# strobe-pcb.net
KiCad netlist of a schematic drawn in EAGLE
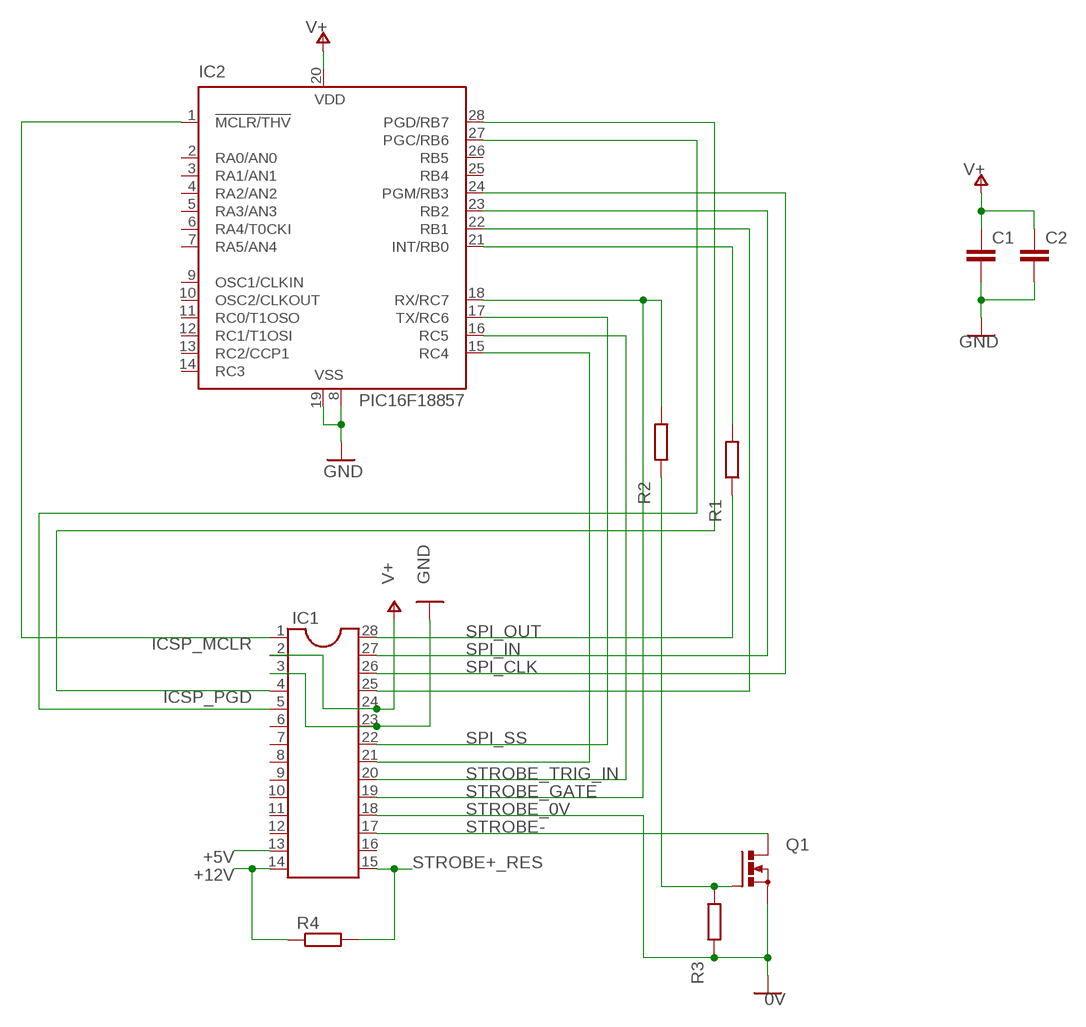
[diagram p0: schematic, sheet 1]

(export (version "E")
  (design (tool "Eeschema 10.0.6"))
  (components
    (comp (ref "C1")
      (value "C-EUC1206")
      (footprint "eagle-import:C1206")
      (libsource (lib "eagle-import") (part "C-EUC1206"))
    )
    (comp (ref "C2")
      (value "C-EUC1206")
      (footprint "eagle-import:C1206")
      (libsource (lib "eagle-import") (part "C-EUC1206"))
    )
    (comp (ref "IC1")
      (value "DIL28")
      (footprint "eagle-import:DIL28-6")
      (libsource (lib "eagle-import") (part "DIL28"))
    )
    (comp (ref "IC2")
      (value "PIC16F18857")
      (footprint "eagle-import:SO28W")
      (fields (field (name "MF") "MICROCHIP") (field (name "MPN") "PIC16F870-I/SO"))
      (libsource (lib "eagle-import") (part "PIC16870SOF"))
    )
    (comp (ref "Q1")
      (value "PMOSFET_NTO220BV")
      (footprint "eagle-import:TO220BV")
      (libsource (lib "eagle-import") (part "PMOSFET_NTO220BV"))
    )
    (comp (ref "R1")
      (value "R-EU_R1206")
      (footprint "eagle-import:R1206")
      (libsource (lib "eagle-import") (part "R-EU_R1206"))
    )
    (comp (ref "R2")
      (value "R-EU_R1206")
      (footprint "eagle-import:R1206")
      (libsource (lib "eagle-import") (part "R-EU_R1206"))
    )
    (comp (ref "R3")
      (value "R-EU_R1206")
      (footprint "eagle-import:R1206")
      (libsource (lib "eagle-import") (part "R-EU_R1206"))
    )
    (comp (ref "R4")
      (value "R-EU_0207/10")
      (footprint "eagle-import:0207_10")
      (libsource (lib "eagle-import") (part "R-EU_0207/10"))
    )
  )
  (nets
    (net (code "1") (name "/+5V") (class "Default")
      (node (ref "IC1") (pin "13") (pinfunction "13_13") (pintype "passive"))
    )
    (net (code "2") (name "/+12V") (class "Default")
      (node (ref "IC1") (pin "14") (pinfunction "14_14") (pintype "passive"))
      (node (ref "R4") (pin "1") (pinfunction "1_1") (pintype "passive"))
    )
    (net (code "3") (name "/ICSP_MCLR") (class "Default")
      (node (ref "IC1") (pin "1") (pinfunction "1_1") (pintype "passive"))
      (node (ref "IC2") (pin "1") (pinfunction "~{MCLR/THV}_1") (pintype "input"))
    )
    (net (code "4") (name "/ICSP_PGD") (class "Default")
      (node (ref "IC1") (pin "4") (pinfunction "4_4") (pintype "passive"))
      (node (ref "IC2") (pin "28") (pinfunction "PGD/RB7_28") (pintype "bidirectional"))
    )
    (net (code "5") (name "/SPI_CLK") (class "Default")
      (node (ref "IC1") (pin "26") (pinfunction "26_26") (pintype "passive"))
      (node (ref "IC2") (pin "24") (pinfunction "PGM/RB3_24") (pintype "bidirectional"))
    )
    (net (code "6") (name "/SPI_IN") (class "Default")
      (node (ref "IC1") (pin "27") (pinfunction "27_27") (pintype "passive"))
      (node (ref "IC2") (pin "23") (pinfunction "RB2_23") (pintype "bidirectional"))
    )
    (net (code "7") (name "/SPI_OUT") (class "Default")
      (node (ref "IC1") (pin "28") (pinfunction "28_28") (pintype "passive"))
      (node (ref "R1") (pin "1") (pinfunction "1_1") (pintype "passive"))
    )
    (net (code "8") (name "/SPI_SS") (class "Default")
      (node (ref "IC1") (pin "22") (pinfunction "22_22") (pintype "passive"))
      (node (ref "IC2") (pin "17") (pinfunction "TX/RC6_17") (pintype "bidirectional"))
    )
    (net (code "9") (name "/STROBE+_RES") (class "Default")
      (node (ref "IC1") (pin "15") (pinfunction "15_15") (pintype "passive"))
      (node (ref "R4") (pin "2") (pinfunction "2_2") (pintype "passive"))
    )
    (net (code "10") (name "/STROBE-") (class "Default")
      (node (ref "IC1") (pin "17") (pinfunction "17_17") (pintype "passive"))
      (node (ref "Q1") (pin "D") (pinfunction "D_D") (pintype "passive"))
    )
    (net (code "11") (name "/STROBE_GATE") (class "Default")
      (node (ref "IC1") (pin "19") (pinfunction "19_19") (pintype "passive"))
      (node (ref "IC2") (pin "18") (pinfunction "RX/RC7_18") (pintype "bidirectional"))
      (node (ref "R2") (pin "2") (pinfunction "2_2") (pintype "passive"))
    )
    (net (code "12") (name "/STROBE_TRIG_IN") (class "Default")
      (node (ref "IC1") (pin "20") (pinfunction "20_20") (pintype "passive"))
      (node (ref "IC2") (pin "16") (pinfunction "RC5_16") (pintype "bidirectional"))
    )
    (net (code "13") (name "0V") (class "Default")
      (node (ref "IC1") (pin "18") (pinfunction "18_18") (pintype "passive"))
      (node (ref "Q1") (pin "S") (pinfunction "S_S") (pintype "passive"))
      (node (ref "R3") (pin "1") (pinfunction "1_1") (pintype "passive"))
    )
    (net (code "14") (name "GND") (class "Default")
      (node (ref "C1") (pin "2") (pinfunction "2_2") (pintype "passive"))
      (node (ref "C2") (pin "2") (pinfunction "2_2") (pintype "passive"))
      (node (ref "IC1") (pin "23") (pinfunction "23_23") (pintype "passive"))
      (node (ref "IC1") (pin "3") (pinfunction "3_3") (pintype "passive"))
      (node (ref "IC2") (pin "19") (pinfunction "VSS_19") (pintype "power_in"))
      (node (ref "IC2") (pin "8") (pinfunction "VSS_8") (pintype "power_in"))
    )
    (net (code "15") (name "Net-(IC2-INT{slash}RB0)") (class "Default")
      (node (ref "IC2") (pin "21") (pinfunction "INT/RB0_21") (pintype "bidirectional"))
      (node (ref "R1") (pin "2") (pinfunction "2_2") (pintype "passive"))
    )
    (net (code "16") (name "Net-(IC2-PGC{slash}RB6)") (class "Default")
      (node (ref "IC1") (pin "5") (pinfunction "5_5") (pintype "passive"))
      (node (ref "IC2") (pin "27") (pinfunction "PGC/RB6_27") (pintype "bidirectional"))
    )
    (net (code "17") (name "Net-(IC2-RB1)") (class "Default")
      (node (ref "IC1") (pin "25") (pinfunction "25_25") (pintype "passive"))
      (node (ref "IC2") (pin "22") (pinfunction "RB1_22") (pintype "bidirectional"))
    )
    (net (code "18") (name "Net-(IC2-RC4)") (class "Default")
      (node (ref "IC1") (pin "21") (pinfunction "21_21") (pintype "passive"))
      (node (ref "IC2") (pin "15") (pinfunction "RC4_15") (pintype "bidirectional"))
    )
    (net (code "19") (name "Net-(Q1-PadG)") (class "Default")
      (node (ref "Q1") (pin "G") (pinfunction "G_G") (pintype "passive"))
      (node (ref "R2") (pin "1") (pinfunction "1_1") (pintype "passive"))
      (node (ref "R3") (pin "2") (pinfunction "2_2") (pintype "passive"))
    )
    (net (code "20") (name "V+") (class "Default")
      (node (ref "C1") (pin "1") (pinfunction "1_1") (pintype "passive"))
      (node (ref "C2") (pin "1") (pinfunction "1_1") (pintype "passive"))
      (node (ref "IC1") (pin "2") (pinfunction "2_2") (pintype "passive"))
      (node (ref "IC1") (pin "24") (pinfunction "24_24") (pintype "passive"))
      (node (ref "IC2") (pin "20") (pinfunction "VDD_20") (pintype "power_in"))
    )
    (net (code "21") (name "unconnected-(IC1-Pad6)") (class "Default")
      (node (ref "IC1") (pin "6") (pinfunction "6_6") (pintype "passive"))
    )
    (net (code "22") (name "unconnected-(IC1-Pad7)") (class "Default")
      (node (ref "IC1") (pin "7") (pinfunction "7_7") (pintype "passive"))
    )
    (net (code "23") (name "unconnected-(IC1-Pad8)") (class "Default")
      (node (ref "IC1") (pin "8") (pinfunction "8_8") (pintype "passive"))
    )
    (net (code "24") (name "unconnected-(IC1-Pad9)") (class "Default")
      (node (ref "IC1") (pin "9") (pinfunction "9_9") (pintype "passive"))
    )
    (net (code "25") (name "unconnected-(IC1-Pad10)") (class "Default")
      (node (ref "IC1") (pin "10") (pinfunction "10_10") (pintype "passive"))
    )
    (net (code "26") (name "unconnected-(IC1-Pad11)") (class "Default")
      (node (ref "IC1") (pin "11") (pinfunction "11_11") (pintype "passive"))
    )
    (net (code "27") (name "unconnected-(IC1-Pad12)") (class "Default")
      (node (ref "IC1") (pin "12") (pinfunction "12_12") (pintype "passive"))
    )
    (net (code "28") (name "unconnected-(IC1-Pad16)") (class "Default")
      (node (ref "IC1") (pin "16") (pinfunction "16_16") (pintype "passive"))
    )
    (net (code "29") (name "unconnected-(IC2-OSC1{slash}CLKIN-Pad9)") (class "Default")
      (node (ref "IC2") (pin "9") (pinfunction "OSC1/CLKIN_9") (pintype "input"))
    )
    (net (code "30") (name "unconnected-(IC2-OSC2{slash}CLKOUT-Pad10)") (class "Default")
      (node (ref "IC2") (pin "10") (pinfunction "OSC2/CLKOUT_10") (pintype "output"))
    )
    (net (code "31") (name "unconnected-(IC2-RA0{slash}AN0-Pad2)") (class "Default")
      (node (ref "IC2") (pin "2") (pinfunction "RA0/AN0_2") (pintype "bidirectional"))
    )
    (net (code "32") (name "unconnected-(IC2-RA1{slash}AN1-Pad3)") (class "Default")
      (node (ref "IC2") (pin "3") (pinfunction "RA1/AN1_3") (pintype "bidirectional"))
    )
    (net (code "33") (name "unconnected-(IC2-RA2{slash}AN2-Pad4)") (class "Default")
      (node (ref "IC2") (pin "4") (pinfunction "RA2/AN2_4") (pintype "bidirectional"))
    )
    (net (code "34") (name "unconnected-(IC2-RA3{slash}AN3-Pad5)") (class "Default")
      (node (ref "IC2") (pin "5") (pinfunction "RA3/AN3_5") (pintype "bidirectional"))
    )
    (net (code "35") (name "unconnected-(IC2-RA4{slash}T0CKI-Pad6)") (class "Default")
      (node (ref "IC2") (pin "6") (pinfunction "RA4/T0CKI_6") (pintype "bidirectional"))
    )
    (net (code "36") (name "unconnected-(IC2-RA5{slash}AN4-Pad7)") (class "Default")
      (node (ref "IC2") (pin "7") (pinfunction "RA5/AN4_7") (pintype "bidirectional"))
    )
    (net (code "37") (name "unconnected-(IC2-RB4-Pad25)") (class "Default")
      (node (ref "IC2") (pin "25") (pinfunction "RB4_25") (pintype "bidirectional"))
    )
    (net (code "38") (name "unconnected-(IC2-RB5-Pad26)") (class "Default")
      (node (ref "IC2") (pin "26") (pinfunction "RB5_26") (pintype "bidirectional"))
    )
    (net (code "39") (name "unconnected-(IC2-RC0{slash}T1OSO-Pad11)") (class "Default")
      (node (ref "IC2") (pin "11") (pinfunction "RC0/T1OSO_11") (pintype "bidirectional"))
    )
    (net (code "40") (name "unconnected-(IC2-RC1{slash}T1OSI-Pad12)") (class "Default")
      (node (ref "IC2") (pin "12") (pinfunction "RC1/T1OSI_12") (pintype "bidirectional"))
    )
    (net (code "41") (name "unconnected-(IC2-RC2{slash}CCP1-Pad13)") (class "Default")
      (node (ref "IC2") (pin "13") (pinfunction "RC2/CCP1_13") (pintype "bidirectional"))
    )
    (net (code "42") (name "unconnected-(IC2-RC3-Pad14)") (class "Default")
      (node (ref "IC2") (pin "14") (pinfunction "RC3_14") (pintype "bidirectional"))
    )
  )
)
